# power_board.net
KiCad netlist of a schematic drawn in EAGLE
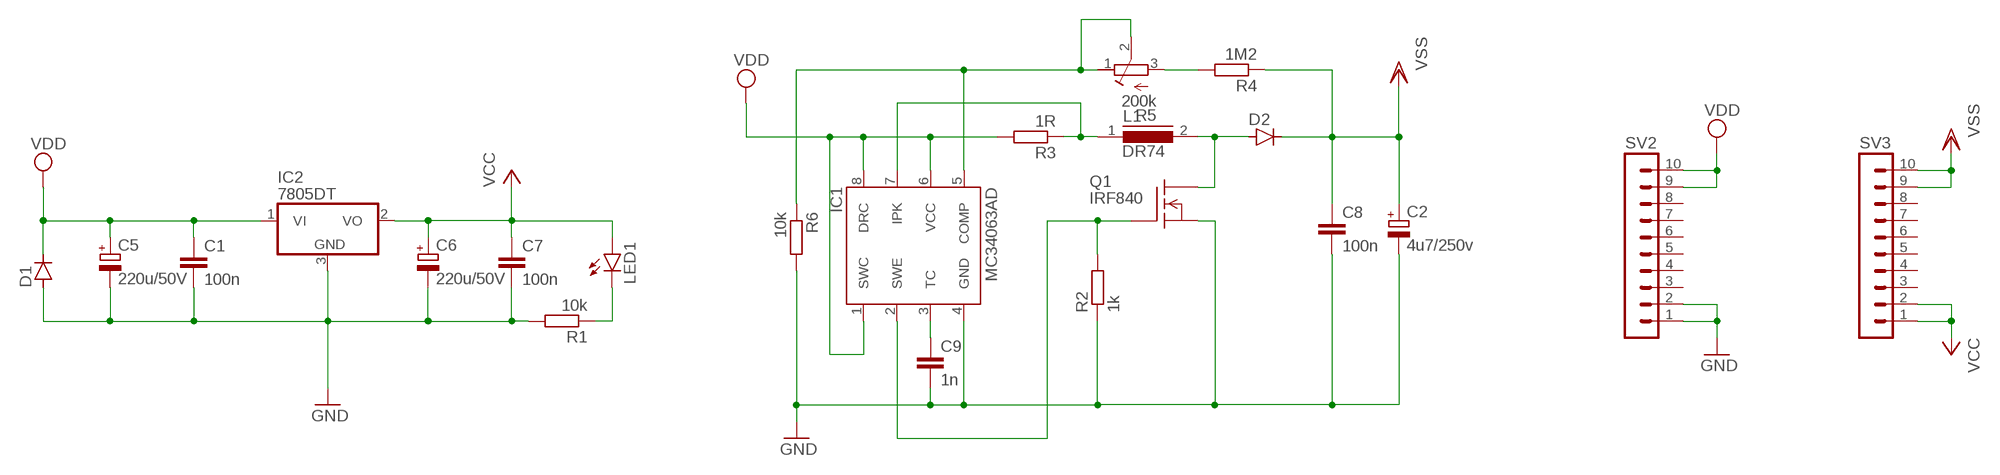
[diagram p0: schematic, sheet 1]

(export (version "E")
  (design (tool "Eeschema 10.0.6"))
  (components
    (comp (ref "C1")
      (value "100n")
      (footprint "eagle-import:C1206")
      (libsource (lib "eagle-import") (part "C-EUC1206"))
    )
    (comp (ref "C2")
      (value "4u7/250v")
      (footprint "eagle-import:E5-10,5")
      (libsource (lib "eagle-import") (part "CPOL-EUE5-10.5"))
    )
    (comp (ref "C5")
      (value "220u/50V")
      (footprint "eagle-import:153CLV-1010")
      (libsource (lib "eagle-import") (part "CPOL-EU153CLV-1010"))
    )
    (comp (ref "C6")
      (value "220u/50V")
      (footprint "eagle-import:153CLV-1010")
      (libsource (lib "eagle-import") (part "CPOL-EU153CLV-1010"))
    )
    (comp (ref "C7")
      (value "100n")
      (footprint "eagle-import:C1206")
      (libsource (lib "eagle-import") (part "C-EUC1206"))
    )
    (comp (ref "C8")
      (value "100n")
      (footprint "eagle-import:C1206")
      (libsource (lib "eagle-import") (part "C-EUC1206"))
    )
    (comp (ref "C9")
      (value "1n")
      (footprint "eagle-import:C1206")
      (libsource (lib "eagle-import") (part "C-EUC1206"))
    )
    (comp (ref "D1")
      (value "D-SOD-80")
      (footprint "eagle-import:SOD80")
      (libsource (lib "eagle-import") (part "D-SOD-80"))
    )
    (comp (ref "D2")
      (value "D-SOD-80")
      (footprint "eagle-import:SOD80")
      (libsource (lib "eagle-import") (part "D-SOD-80"))
    )
    (comp (ref "IC1")
      (value "MC34063AD")
      (footprint "eagle-import:SO08")
      (libsource (lib "eagle-import") (part "MC34063AD"))
    )
    (comp (ref "IC2")
      (value "7805DT")
      (footprint "eagle-import:TO252")
      (libsource (lib "eagle-import") (part "78DT05"))
    )
    (comp (ref "L1")
      (value "DR74")
      (footprint "eagle-import:DR74")
      (libsource (lib "eagle-import") (part "DR74"))
    )
    (comp (ref "LED1")
      (value "LEDSMT1206")
      (footprint "eagle-import:1206")
      (libsource (lib "eagle-import") (part "LEDSMT1206"))
    )
    (comp (ref "Q1")
      (value "IRF840")
      (footprint "eagle-import:TO220")
      (libsource (lib "eagle-import") (part "IRF840"))
    )
    (comp (ref "R1")
      (value "10k")
      (footprint "eagle-import:R1206")
      (libsource (lib "eagle-import") (part "R-EU_R1206"))
    )
    (comp (ref "R2")
      (value "1k")
      (footprint "eagle-import:R1206")
      (libsource (lib "eagle-import") (part "R-EU_R1206"))
    )
    (comp (ref "R3")
      (value "1R")
      (footprint "eagle-import:R1206")
      (libsource (lib "eagle-import") (part "R-EU_R1206"))
    )
    (comp (ref "R4")
      (value "1M2")
      (footprint "eagle-import:R1206")
      (libsource (lib "eagle-import") (part "R-EU_R1206"))
    )
    (comp (ref "R5")
      (value "200k")
      (footprint "eagle-import:RTRIM43P")
      (libsource (lib "eagle-import") (part "R-TRIMM43P"))
    )
    (comp (ref "R6")
      (value "10k")
      (footprint "eagle-import:R1206")
      (libsource (lib "eagle-import") (part "R-EU_R1206"))
    )
    (comp (ref "SV2")
      (value "MA10-1")
      (footprint "eagle-import:MA10-1")
      (libsource (lib "eagle-import") (part "MA10-1"))
    )
    (comp (ref "SV3")
      (value "MA10-1")
      (footprint "eagle-import:MA10-1")
      (libsource (lib "eagle-import") (part "MA10-1"))
    )
  )
  (nets
    (net (code "1") (name "GND") (class "Default")
      (node (ref "C1") (pin "2") (pinfunction "2_2") (pintype "passive"))
      (node (ref "C2") (pin "-") (pinfunction "-_-") (pintype "passive"))
      (node (ref "C5") (pin "-") (pinfunction "-_-") (pintype "passive"))
      (node (ref "C6") (pin "-") (pinfunction "-_-") (pintype "passive"))
      (node (ref "C7") (pin "2") (pinfunction "2_2") (pintype "passive"))
      (node (ref "C8") (pin "2") (pinfunction "2_2") (pintype "passive"))
      (node (ref "C9") (pin "2") (pinfunction "2_2") (pintype "passive"))
      (node (ref "D1") (pin "2") (pinfunction "A_2") (pintype "passive"))
      (node (ref "IC1") (pin "4") (pinfunction "GND_4") (pintype "power_in"))
      (node (ref "IC2") (pin "3") (pinfunction "GND_3") (pintype "passive"))
      (node (ref "Q1") (pin "3") (pinfunction "S_3") (pintype "passive"))
      (node (ref "R1") (pin "2") (pinfunction "2_2") (pintype "passive"))
      (node (ref "R2") (pin "1") (pinfunction "1_1") (pintype "passive"))
      (node (ref "R6") (pin "2") (pinfunction "2_2") (pintype "passive"))
      (node (ref "SV2") (pin "1") (pinfunction "1_1") (pintype "passive"))
      (node (ref "SV2") (pin "2") (pinfunction "2_2") (pintype "passive"))
    )
    (net (code "2") (name "Net-(D2-A)") (class "Default")
      (node (ref "D2") (pin "2") (pinfunction "A_2") (pintype "passive"))
      (node (ref "L1") (pin "2") (pinfunction "2_2") (pintype "passive"))
      (node (ref "Q1") (pin "2") (pinfunction "D_2") (pintype "passive"))
    )
    (net (code "3") (name "Net-(IC1-COMP)") (class "Default")
      (node (ref "IC1") (pin "5") (pinfunction "COMP_5") (pintype "input"))
      (node (ref "R5") (pin "1") (pinfunction "E_1") (pintype "passive"))
      (node (ref "R5") (pin "2") (pinfunction "S_2") (pintype "passive"))
      (node (ref "R6") (pin "1") (pinfunction "1_1") (pintype "passive"))
    )
    (net (code "4") (name "Net-(IC1-IPK)") (class "Default")
      (node (ref "IC1") (pin "7") (pinfunction "IPK_7") (pintype "input"))
      (node (ref "L1") (pin "1") (pinfunction "1_1") (pintype "passive"))
      (node (ref "R3") (pin "1") (pinfunction "1_1") (pintype "passive"))
    )
    (net (code "5") (name "Net-(IC1-SWE)") (class "Default")
      (node (ref "IC1") (pin "2") (pinfunction "SWE_2") (pintype "bidirectional"))
      (node (ref "Q1") (pin "1") (pinfunction "G_1") (pintype "passive"))
      (node (ref "R2") (pin "2") (pinfunction "2_2") (pintype "passive"))
    )
    (net (code "6") (name "Net-(IC1-TC)") (class "Default")
      (node (ref "C9") (pin "1") (pinfunction "1_1") (pintype "passive"))
      (node (ref "IC1") (pin "3") (pinfunction "TC_3") (pintype "passive"))
    )
    (net (code "7") (name "Net-(LED1-PadC)") (class "Default")
      (node (ref "LED1") (pin "C") (pinfunction "C_C") (pintype "passive"))
      (node (ref "R1") (pin "1") (pinfunction "1_1") (pintype "passive"))
    )
    (net (code "8") (name "Net-(R5-A)") (class "Default")
      (node (ref "R4") (pin "2") (pinfunction "2_2") (pintype "passive"))
      (node (ref "R5") (pin "3") (pinfunction "A_3") (pintype "passive"))
    )
    (net (code "9") (name "VCC") (class "Default")
      (node (ref "C6") (pin "+") (pinfunction "+_+") (pintype "passive"))
      (node (ref "C7") (pin "1") (pinfunction "1_1") (pintype "passive"))
      (node (ref "IC2") (pin "2") (pinfunction "VO_2") (pintype "passive"))
      (node (ref "LED1") (pin "A") (pinfunction "A_A") (pintype "passive"))
      (node (ref "SV3") (pin "1") (pinfunction "1_1") (pintype "passive"))
      (node (ref "SV3") (pin "2") (pinfunction "2_2") (pintype "passive"))
    )
    (net (code "10") (name "VDD") (class "Default")
      (node (ref "C1") (pin "1") (pinfunction "1_1") (pintype "passive"))
      (node (ref "C5") (pin "+") (pinfunction "+_+") (pintype "passive"))
      (node (ref "D1") (pin "1") (pinfunction "C_1") (pintype "passive"))
      (node (ref "IC1") (pin "1") (pinfunction "SWC_1") (pintype "bidirectional"))
      (node (ref "IC1") (pin "6") (pinfunction "VCC_6") (pintype "power_in"))
      (node (ref "IC1") (pin "8") (pinfunction "DRC_8") (pintype "input"))
      (node (ref "IC2") (pin "1") (pinfunction "VI_1") (pintype "input"))
      (node (ref "R3") (pin "2") (pinfunction "2_2") (pintype "passive"))
      (node (ref "SV2") (pin "10") (pinfunction "10_10") (pintype "passive"))
      (node (ref "SV2") (pin "9") (pinfunction "9_9") (pintype "passive"))
    )
    (net (code "11") (name "VSS") (class "Default")
      (node (ref "C2") (pin "+") (pinfunction "+_+") (pintype "passive"))
      (node (ref "C8") (pin "1") (pinfunction "1_1") (pintype "passive"))
      (node (ref "D2") (pin "1") (pinfunction "C_1") (pintype "passive"))
      (node (ref "R4") (pin "1") (pinfunction "1_1") (pintype "passive"))
      (node (ref "SV3") (pin "10") (pinfunction "10_10") (pintype "passive"))
      (node (ref "SV3") (pin "9") (pinfunction "9_9") (pintype "passive"))
    )
    (net (code "12") (name "unconnected-(SV2-Pad3)") (class "Default")
      (node (ref "SV2") (pin "3") (pinfunction "3_3") (pintype "passive"))
    )
    (net (code "13") (name "unconnected-(SV2-Pad4)") (class "Default")
      (node (ref "SV2") (pin "4") (pinfunction "4_4") (pintype "passive"))
    )
    (net (code "14") (name "unconnected-(SV2-Pad5)") (class "Default")
      (node (ref "SV2") (pin "5") (pinfunction "5_5") (pintype "passive"))
    )
    (net (code "15") (name "unconnected-(SV2-Pad6)") (class "Default")
      (node (ref "SV2") (pin "6") (pinfunction "6_6") (pintype "passive"))
    )
    (net (code "16") (name "unconnected-(SV2-Pad7)") (class "Default")
      (node (ref "SV2") (pin "7") (pinfunction "7_7") (pintype "passive"))
    )
    (net (code "17") (name "unconnected-(SV2-Pad8)") (class "Default")
      (node (ref "SV2") (pin "8") (pinfunction "8_8") (pintype "passive"))
    )
    (net (code "18") (name "unconnected-(SV3-Pad3)") (class "Default")
      (node (ref "SV3") (pin "3") (pinfunction "3_3") (pintype "passive"))
    )
    (net (code "19") (name "unconnected-(SV3-Pad4)") (class "Default")
      (node (ref "SV3") (pin "4") (pinfunction "4_4") (pintype "passive"))
    )
    (net (code "20") (name "unconnected-(SV3-Pad5)") (class "Default")
      (node (ref "SV3") (pin "5") (pinfunction "5_5") (pintype "passive"))
    )
    (net (code "21") (name "unconnected-(SV3-Pad6)") (class "Default")
      (node (ref "SV3") (pin "6") (pinfunction "6_6") (pintype "passive"))
    )
    (net (code "22") (name "unconnected-(SV3-Pad7)") (class "Default")
      (node (ref "SV3") (pin "7") (pinfunction "7_7") (pintype "passive"))
    )
    (net (code "23") (name "unconnected-(SV3-Pad8)") (class "Default")
      (node (ref "SV3") (pin "8") (pinfunction "8_8") (pintype "passive"))
    )
  )
)
